# Schematic.net
KiCad netlist of a schematic drawn in Altium Designer
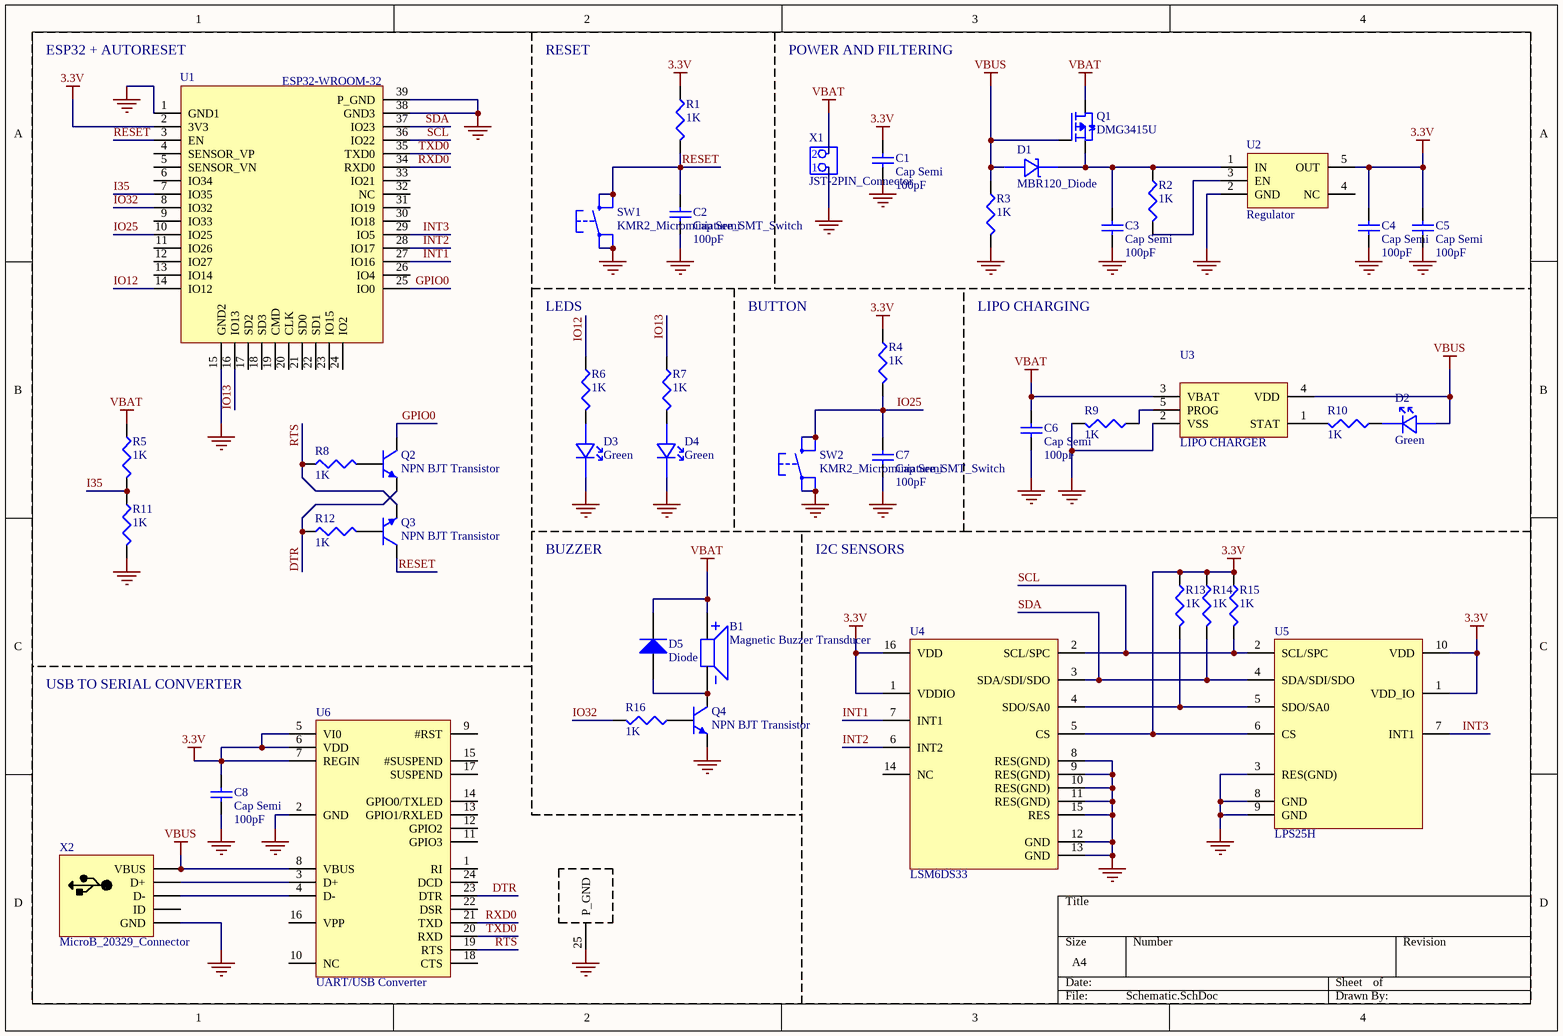
[diagram p0: Schematic.SchDoc]

(export (version "E")
  (design (tool "Eeschema 10.0.6"))
  (components
    (comp (ref "B1")
      (value "Magnetic Buzzer Transducer")
      (footprint "CMT-0502 Buzzer")
      (libsource (lib "Custom WROOM32 Board Library") (part "CMT-0502-75-SMT-TR"))
    )
    (comp (ref "C1")
      (value "Cap Semi")
      (footprint "J1-0603")
      (description "Capacitor (Semiconductor SIM Model)")
      (fields (field (name "ALTIUM_VALUE") "100pF") (field (name "PUBLISHER") "Altium Limited"))
      (libsource (lib "Miscellaneous Devices") (part "Cap Semi"))
    )
    (comp (ref "C2")
      (value "Cap Semi")
      (footprint "J1-0603")
      (description "Capacitor (Semiconductor SIM Model)")
      (fields (field (name "ALTIUM_VALUE") "100pF") (field (name "PUBLISHER") "Altium Limited"))
      (libsource (lib "Miscellaneous Devices") (part "Cap Semi"))
    )
    (comp (ref "C3")
      (value "Cap Semi")
      (footprint "J1-0603")
      (description "Capacitor (Semiconductor SIM Model)")
      (fields (field (name "ALTIUM_VALUE") "100pF") (field (name "PUBLISHER") "Altium Limited"))
      (libsource (lib "Miscellaneous Devices") (part "Cap Semi"))
    )
    (comp (ref "C4")
      (value "Cap Semi")
      (footprint "J1-0603")
      (description "Capacitor (Semiconductor SIM Model)")
      (fields (field (name "ALTIUM_VALUE") "100pF") (field (name "PUBLISHER") "Altium Limited"))
      (libsource (lib "Miscellaneous Devices") (part "Cap Semi"))
    )
    (comp (ref "C5")
      (value "Cap Semi")
      (footprint "J1-0603")
      (description "Capacitor (Semiconductor SIM Model)")
      (fields (field (name "ALTIUM_VALUE") "100pF") (field (name "PUBLISHER") "Altium Limited"))
      (libsource (lib "Miscellaneous Devices") (part "Cap Semi"))
    )
    (comp (ref "C6")
      (value "Cap Semi")
      (footprint "J1-0603")
      (description "Capacitor (Semiconductor SIM Model)")
      (fields (field (name "ALTIUM_VALUE") "100pF") (field (name "PUBLISHER") "Altium Limited"))
      (libsource (lib "Miscellaneous Devices") (part "Cap Semi"))
    )
    (comp (ref "C7")
      (value "Cap Semi")
      (footprint "J1-0603")
      (description "Capacitor (Semiconductor SIM Model)")
      (fields (field (name "ALTIUM_VALUE") "100pF") (field (name "PUBLISHER") "Altium Limited"))
      (libsource (lib "Miscellaneous Devices") (part "Cap Semi"))
    )
    (comp (ref "C8")
      (value "Cap Semi")
      (footprint "J1-0603")
      (description "Capacitor (Semiconductor SIM Model)")
      (fields (field (name "ALTIUM_VALUE") "100pF") (field (name "PUBLISHER") "Altium Limited"))
      (libsource (lib "Miscellaneous Devices") (part "Cap Semi"))
    )
    (comp (ref "D1")
      (value "MBR120_Diode")
      (footprint "SML_LED")
      (libsource (lib "Custom WROOM32 Board Library") (part "MBR120_Diode"))
    )
    (comp (ref "D2")
      (value "Green")
      (footprint "SML_LED")
      (libsource (lib "Custom WROOM32 Board Library") (part "SML-LX0603GW-TR_LED_Diode"))
    )
    (comp (ref "D3")
      (value "Green")
      (footprint "SML_LED")
      (libsource (lib "Custom WROOM32 Board Library") (part "SML-LX0603GW-TR_LED_Diode"))
    )
    (comp (ref "D4")
      (value "Green")
      (footprint "SML_LED")
      (libsource (lib "Custom WROOM32 Board Library") (part "SML-LX0603GW-TR_LED_Diode"))
    )
    (comp (ref "D5")
      (value "Diode")
      (footprint "SML_LED")
      (description "Default Diode")
      (fields (field (name "PUBLISHER") "Altium Limited"))
      (libsource (lib "Miscellaneous Devices") (part "Diode"))
    )
    (comp (ref "Q1")
      (value "DMG3415U")
      (footprint "SOT323")
      (libsource (lib "Custom WROOM32 Board Library") (part "DMG3415U"))
    )
    (comp (ref "Q2")
      (value "NPN BJT Transistor")
      (footprint "SOT323")
      (libsource (lib "Custom WROOM32 Board Library") (part "2sd1484k"))
    )
    (comp (ref "Q3")
      (value "NPN BJT Transistor")
      (footprint "SOT323")
      (libsource (lib "Custom WROOM32 Board Library") (part "2sd1484k"))
    )
    (comp (ref "Q4")
      (value "NPN BJT Transistor")
      (footprint "SOT323")
      (libsource (lib "Custom WROOM32 Board Library") (part "2sd1484k"))
    )
    (comp (ref "R1")
      (value "1K")
      (footprint "J1-0603")
      (description "Resistor")
      (fields (field (name "Comment") "Res3") (field (name "PUBLISHER") "Altium Limited"))
      (libsource (lib "Miscellaneous Devices") (part "Res3"))
    )
    (comp (ref "R2")
      (value "1K")
      (footprint "J1-0603")
      (description "Resistor")
      (fields (field (name "Comment") "Res3") (field (name "PUBLISHER") "Altium Limited"))
      (libsource (lib "Miscellaneous Devices") (part "Res3"))
    )
    (comp (ref "R3")
      (value "1K")
      (footprint "J1-0603")
      (description "Resistor")
      (fields (field (name "Comment") "Res3") (field (name "PUBLISHER") "Altium Limited"))
      (libsource (lib "Miscellaneous Devices") (part "Res3"))
    )
    (comp (ref "R4")
      (value "1K")
      (footprint "J1-0603")
      (description "Resistor")
      (fields (field (name "Comment") "Res3") (field (name "PUBLISHER") "Altium Limited"))
      (libsource (lib "Miscellaneous Devices") (part "Res3"))
    )
    (comp (ref "R5")
      (value "1K")
      (footprint "J1-0603")
      (description "Resistor")
      (fields (field (name "Comment") "Res3") (field (name "PUBLISHER") "Altium Limited"))
      (libsource (lib "Miscellaneous Devices") (part "Res3"))
    )
    (comp (ref "R6")
      (value "1K")
      (footprint "J1-0603")
      (description "Resistor")
      (fields (field (name "Comment") "Res3") (field (name "PUBLISHER") "Altium Limited"))
      (libsource (lib "Miscellaneous Devices") (part "Res3"))
    )
    (comp (ref "R7")
      (value "1K")
      (footprint "J1-0603")
      (description "Resistor")
      (fields (field (name "Comment") "Res3") (field (name "PUBLISHER") "Altium Limited"))
      (libsource (lib "Miscellaneous Devices") (part "Res3"))
    )
    (comp (ref "R8")
      (value "1K")
      (footprint "J1-0603")
      (description "Resistor")
      (fields (field (name "Comment") "Res3") (field (name "PUBLISHER") "Altium Limited"))
      (libsource (lib "Miscellaneous Devices") (part "Res3"))
    )
    (comp (ref "R9")
      (value "1K")
      (footprint "J1-0603")
      (description "Resistor")
      (fields (field (name "Comment") "Res3") (field (name "PUBLISHER") "Altium Limited"))
      (libsource (lib "Miscellaneous Devices") (part "Res3"))
    )
    (comp (ref "R10")
      (value "1K")
      (footprint "J1-0603")
      (description "Resistor")
      (fields (field (name "Comment") "Res3") (field (name "PUBLISHER") "Altium Limited"))
      (libsource (lib "Miscellaneous Devices") (part "Res3"))
    )
    (comp (ref "R11")
      (value "1K")
      (footprint "J1-0603")
      (description "Resistor")
      (fields (field (name "Comment") "Res3") (field (name "PUBLISHER") "Altium Limited"))
      (libsource (lib "Miscellaneous Devices") (part "Res3"))
    )
    (comp (ref "R12")
      (value "1K")
      (footprint "J1-0603")
      (description "Resistor")
      (fields (field (name "Comment") "Res3") (field (name "PUBLISHER") "Altium Limited"))
      (libsource (lib "Miscellaneous Devices") (part "Res3"))
    )
    (comp (ref "R13")
      (value "1K")
      (footprint "J1-0603")
      (description "Resistor")
      (fields (field (name "Comment") "Res3") (field (name "PUBLISHER") "Altium Limited"))
      (libsource (lib "Miscellaneous Devices") (part "Res3"))
    )
    (comp (ref "R14")
      (value "1K")
      (footprint "J1-0603")
      (description "Resistor")
      (fields (field (name "Comment") "Res3") (field (name "PUBLISHER") "Altium Limited"))
      (libsource (lib "Miscellaneous Devices") (part "Res3"))
    )
    (comp (ref "R15")
      (value "1K")
      (footprint "J1-0603")
      (description "Resistor")
      (fields (field (name "Comment") "Res3") (field (name "PUBLISHER") "Altium Limited"))
      (libsource (lib "Miscellaneous Devices") (part "Res3"))
    )
    (comp (ref "R16")
      (value "1K")
      (footprint "J1-0603")
      (description "Resistor")
      (fields (field (name "Comment") "Res3") (field (name "PUBLISHER") "Altium Limited"))
      (libsource (lib "Miscellaneous Devices") (part "Res3"))
    )
    (comp (ref "SW1")
      (value "KMR2_Microminiature_SMT_Switch")
      (footprint "KMR 2 Microswitch")
      (libsource (lib "Custom WROOM32 Board Library") (part "KMR2_Microminiature_SMT_Switch"))
    )
    (comp (ref "SW2")
      (value "KMR2_Microminiature_SMT_Switch")
      (footprint "KMR 2 Microswitch")
      (libsource (lib "Custom WROOM32 Board Library") (part "KMR2_Microminiature_SMT_Switch"))
    )
    (comp (ref "U1")
      (value "ESP32-WROOM-32")
      (footprint "ESP_WROOM_32")
      (libsource (lib "Custom WROOM32 Board Library") (part "ESP32-WROOM-32"))
    )
    (comp (ref "U2")
      (value "Regulator")
      (footprint "SOT25")
      (libsource (lib "Custom WROOM32 Board Library") (part "AP2112-3.3"))
    )
    (comp (ref "U3")
      (value "LIPO CHARGER")
      (footprint "SOT-23")
      (libsource (lib "Custom WROOM32 Board Library") (part "MCP7381/2"))
    )
    (comp (ref "U4")
      (value "LSM6DS33")
      (footprint "LSM6DS33")
      (libsource (lib "Custom WROOM32 Board Library") (part "LSM6DS33"))
    )
    (comp (ref "U5")
      (value "LPS25H")
      (footprint "LPS25HB")
      (libsource (lib "Custom WROOM32 Board Library") (part "LPS25H"))
    )
    (comp (ref "U6")
      (value "UART/USB Converter")
      (footprint "CP2104-GM")
      (libsource (lib "Custom WROOM32 Board Library") (part "CP2104"))
    )
    (comp (ref "X1")
      (value "JST-2PIN_Connector")
      (footprint "JST-2PIN")
      (libsource (lib "Custom WROOM32 Board Library") (part "JST-2PIN_Connector"))
    )
    (comp (ref "X2")
      (value "MicroB_20329_Connector")
      (footprint "Micro_B_USB_smd")
      (libsource (lib "Custom WROOM32 Board Library") (part "MicroB_20329_Connector"))
    )
  )
  (nets
    (net (code "1") (name "/DTR") (class "Default")
      (node (ref "Q2") (pin "1") (pinfunction "E_1") (pintype "passive"))
      (node (ref "R12") (pin "1") (pinfunction "1_1") (pintype "passive"))
      (node (ref "U6") (pin "23") (pinfunction "DTR_23") (pintype "passive"))
    )
    (net (code "2") (name "/GPIO0") (class "Default")
      (node (ref "Q2") (pin "3") (pinfunction "C_3") (pintype "passive"))
      (node (ref "U1") (pin "25") (pinfunction "IO0_25") (pintype "passive"))
    )
    (net (code "3") (name "/I35") (class "Default")
      (node (ref "R11") (pin "1") (pinfunction "1_1") (pintype "passive"))
      (node (ref "R5") (pin "2") (pinfunction "2_2") (pintype "passive"))
      (node (ref "U1") (pin "7") (pinfunction "IO35_7") (pintype "passive"))
    )
    (net (code "4") (name "/INT1") (class "Default")
      (node (ref "U1") (pin "27") (pinfunction "IO16_27") (pintype "passive"))
      (node (ref "U4") (pin "7") (pinfunction "INT1_7") (pintype "passive"))
    )
    (net (code "5") (name "/INT2") (class "Default")
      (node (ref "U1") (pin "28") (pinfunction "IO17_28") (pintype "passive"))
      (node (ref "U4") (pin "6") (pinfunction "INT2_6") (pintype "passive"))
    )
    (net (code "6") (name "/INT3") (class "Default")
      (node (ref "U1") (pin "29") (pinfunction "IO5_29") (pintype "passive"))
      (node (ref "U5") (pin "7") (pinfunction "INT1_7") (pintype "passive"))
    )
    (net (code "7") (name "/IO12") (class "Default")
      (node (ref "R6") (pin "1") (pinfunction "1_1") (pintype "passive"))
      (node (ref "U1") (pin "14") (pinfunction "IO12_14") (pintype "passive"))
    )
    (net (code "8") (name "/IO13") (class "Default")
      (node (ref "R7") (pin "1") (pinfunction "1_1") (pintype "passive"))
      (node (ref "U1") (pin "16") (pinfunction "IO13_16") (pintype "passive"))
    )
    (net (code "9") (name "/IO25") (class "Default")
      (node (ref "C7") (pin "2") (pinfunction "2_2") (pintype "passive"))
      (node (ref "R4") (pin "2") (pinfunction "2_2") (pintype "passive"))
      (node (ref "SW2") (pin "1") (pinfunction "1_1") (pintype "passive"))
      (node (ref "SW2") (pin "2") (pinfunction "2_2") (pintype "passive"))
      (node (ref "U1") (pin "10") (pinfunction "IO25_10") (pintype "passive"))
    )
    (net (code "10") (name "/IO32") (class "Default")
      (node (ref "R16") (pin "2") (pinfunction "2_2") (pintype "passive"))
      (node (ref "U1") (pin "8") (pinfunction "IO32_8") (pintype "passive"))
    )
    (net (code "11") (name "/RESET") (class "Default")
      (node (ref "C2") (pin "2") (pinfunction "2_2") (pintype "passive"))
      (node (ref "Q3") (pin "3") (pinfunction "C_3") (pintype "passive"))
      (node (ref "R1") (pin "2") (pinfunction "2_2") (pintype "passive"))
      (node (ref "SW1") (pin "1") (pinfunction "1_1") (pintype "passive"))
      (node (ref "SW1") (pin "2") (pinfunction "2_2") (pintype "passive"))
      (node (ref "U1") (pin "3") (pinfunction "EN_3") (pintype "passive"))
    )
    (net (code "12") (name "/RTS") (class "Default")
      (node (ref "Q3") (pin "1") (pinfunction "E_1") (pintype "passive"))
      (node (ref "R8") (pin "1") (pinfunction "1_1") (pintype "passive"))
      (node (ref "U6") (pin "19") (pinfunction "RTS_19") (pintype "passive"))
    )
    (net (code "13") (name "/RXD0") (class "Default")
      (node (ref "U1") (pin "34") (pinfunction "RXD0_34") (pintype "passive"))
      (node (ref "U6") (pin "21") (pinfunction "TXD_21") (pintype "passive"))
    )
    (net (code "14") (name "/SCL") (class "Default")
      (node (ref "R15") (pin "1") (pinfunction "1_1") (pintype "passive"))
      (node (ref "U1") (pin "36") (pinfunction "IO22_36") (pintype "passive"))
      (node (ref "U4") (pin "2") (pinfunction "SCL/SPC_2") (pintype "passive"))
      (node (ref "U5") (pin "2") (pinfunction "SCL/SPC_2") (pintype "passive"))
    )
    (net (code "15") (name "/SDA") (class "Default")
      (node (ref "R14") (pin "1") (pinfunction "1_1") (pintype "passive"))
      (node (ref "U1") (pin "37") (pinfunction "IO23_37") (pintype "passive"))
      (node (ref "U4") (pin "3") (pinfunction "SDA/SDI/SDO_3") (pintype "passive"))
      (node (ref "U5") (pin "4") (pinfunction "SDA/SDI/SDO_4") (pintype "passive"))
    )
    (net (code "16") (name "/TXD0") (class "Default")
      (node (ref "U1") (pin "35") (pinfunction "TXD0_35") (pintype "passive"))
      (node (ref "U6") (pin "20") (pinfunction "RXD_20") (pintype "passive"))
    )
    (net (code "17") (name "3.3V") (class "Default")
      (node (ref "C1") (pin "2") (pinfunction "2_2") (pintype "passive"))
      (node (ref "C4") (pin "2") (pinfunction "2_2") (pintype "passive"))
      (node (ref "C5") (pin "2") (pinfunction "2_2") (pintype "passive"))
      (node (ref "C8") (pin "2") (pinfunction "2_2") (pintype "passive"))
      (node (ref "R1") (pin "1") (pinfunction "1_1") (pintype "passive"))
      (node (ref "R13") (pin "2") (pinfunction "2_2") (pintype "passive"))
      (node (ref "R14") (pin "2") (pinfunction "2_2") (pintype "passive"))
      (node (ref "R15") (pin "2") (pinfunction "2_2") (pintype "passive"))
      (node (ref "R4") (pin "1") (pinfunction "1_1") (pintype "passive"))
      (node (ref "U1") (pin "2") (pinfunction "3V3_2") (pintype "passive"))
      (node (ref "U2") (pin "5") (pinfunction "OUT_5") (pintype "passive"))
      (node (ref "U4") (pin "1") (pinfunction "VDDIO_1") (pintype "passive"))
      (node (ref "U4") (pin "16") (pinfunction "VDD_16") (pintype "passive"))
      (node (ref "U4") (pin "5") (pinfunction "CS_5") (pintype "passive"))
      (node (ref "U5") (pin "1") (pinfunction "VDD_IO_1") (pintype "passive"))
      (node (ref "U5") (pin "10") (pinfunction "VDD_10") (pintype "passive"))
      (node (ref "U5") (pin "6") (pinfunction "CS_6") (pintype "passive"))
      (node (ref "U6") (pin "5") (pinfunction "VI0_5") (pintype "passive"))
      (node (ref "U6") (pin "6") (pinfunction "VDD_6") (pintype "passive"))
      (node (ref "U6") (pin "7") (pinfunction "REGIN_7") (pintype "passive"))
    )
    (net (code "18") (name "GND") (class "Default")
      (node (ref "C1") (pin "1") (pinfunction "1_1") (pintype "passive"))
      (node (ref "C2") (pin "1") (pinfunction "1_1") (pintype "passive"))
      (node (ref "C3") (pin "1") (pinfunction "1_1") (pintype "passive"))
      (node (ref "C4") (pin "1") (pinfunction "1_1") (pintype "passive"))
      (node (ref "C5") (pin "1") (pinfunction "1_1") (pintype "passive"))
      (node (ref "C6") (pin "1") (pinfunction "1_1") (pintype "passive"))
      (node (ref "C7") (pin "1") (pinfunction "1_1") (pintype "passive"))
      (node (ref "C8") (pin "1") (pinfunction "1_1") (pintype "passive"))
      (node (ref "D3") (pin "2") (pinfunction "K_2") (pintype "passive"))
      (node (ref "D4") (pin "2") (pinfunction "K_2") (pintype "passive"))
      (node (ref "Q4") (pin "1") (pinfunction "E_1") (pintype "passive"))
      (node (ref "R11") (pin "2") (pinfunction "2_2") (pintype "passive"))
      (node (ref "R3") (pin "2") (pinfunction "2_2") (pintype "passive"))
      (node (ref "R9") (pin "1") (pinfunction "1_1") (pintype "passive"))
      (node (ref "SW1") (pin "3") (pinfunction "3_3") (pintype "passive"))
      (node (ref "SW1") (pin "4") (pinfunction "4_4") (pintype "passive"))
      (node (ref "SW2") (pin "3") (pinfunction "3_3") (pintype "passive"))
      (node (ref "SW2") (pin "4") (pinfunction "4_4") (pintype "passive"))
      (node (ref "U1") (pin "1") (pinfunction "GND1_1") (pintype "passive"))
      (node (ref "U1") (pin "15") (pinfunction "GND2_15") (pintype "passive"))
      (node (ref "U1") (pin "38") (pinfunction "GND3_38") (pintype "passive"))
      (node (ref "U1") (pin "39") (pinfunction "P_GND_39") (pintype "passive"))
      (node (ref "U2") (pin "2") (pinfunction "GND_2") (pintype "passive"))
      (node (ref "U3") (pin "2") (pinfunction "VSS_2") (pintype "passive"))
      (node (ref "U4") (pin "10") (pinfunction "RES(GND)_10") (pintype "passive"))
      (node (ref "U4") (pin "11") (pinfunction "RES(GND)_11") (pintype "passive"))
      (node (ref "U4") (pin "12") (pinfunction "GND_12") (pintype "passive"))
      (node (ref "U4") (pin "13") (pinfunction "GND_13") (pintype "passive"))
      (node (ref "U4") (pin "15") (pinfunction "RES_15") (pintype "passive"))
      (node (ref "U4") (pin "8") (pinfunction "RES(GND)_8") (pintype "passive"))
      (node (ref "U4") (pin "9") (pinfunction "RES(GND)_9") (pintype "passive"))
      (node (ref "U5") (pin "3") (pinfunction "RES(GND)_3") (pintype "passive"))
      (node (ref "U5") (pin "8") (pinfunction "GND_8") (pintype "passive"))
      (node (ref "U5") (pin "9") (pinfunction "GND_9") (pintype "passive"))
      (node (ref "U6") (pin "2") (pinfunction "GND_2") (pintype "passive"))
      (node (ref "U6") (pin "25") (pinfunction "P_GND_25") (pintype "passive"))
      (node (ref "X1") (pin "1") (pinfunction "1_1") (pintype "passive"))
      (node (ref "X2") (pin "5") (pinfunction "GND_5") (pintype "passive"))
    )
    (net (code "19") (name "Net-(B1--)") (class "Default")
      (node (ref "B1") (pin "2") (pinfunction "-_2") (pintype "passive"))
      (node (ref "D5") (pin "1") (pinfunction "A_1") (pintype "passive"))
      (node (ref "Q4") (pin "3") (pinfunction "C_3") (pintype "passive"))
    )
    (net (code "20") (name "Net-(D1-K)") (class "Default")
      (node (ref "C3") (pin "2") (pinfunction "2_2") (pintype "passive"))
      (node (ref "D1") (pin "2") (pinfunction "K_2") (pintype "passive"))
      (node (ref "Q1") (pin "3") (pinfunction "S_3") (pintype "passive"))
      (node (ref "R2") (pin "1") (pinfunction "1_1") (pintype "passive"))
      (node (ref "U2") (pin "1") (pinfunction "IN_1") (pintype "passive"))
    )
    (net (code "21") (name "Net-(D2-K)") (class "Default")
      (node (ref "D2") (pin "2") (pinfunction "K_2") (pintype "passive"))
      (node (ref "R10") (pin "2") (pinfunction "2_2") (pintype "passive"))
    )
    (net (code "22") (name "Net-(D3-A)") (class "Default")
      (node (ref "D3") (pin "1") (pinfunction "A_1") (pintype "passive"))
      (node (ref "R6") (pin "2") (pinfunction "2_2") (pintype "passive"))
    )
    (net (code "23") (name "Net-(D4-A)") (class "Default")
      (node (ref "D4") (pin "1") (pinfunction "A_1") (pintype "passive"))
      (node (ref "R7") (pin "2") (pinfunction "2_2") (pintype "passive"))
    )
    (net (code "24") (name "Net-(Q2-B)") (class "Default")
      (node (ref "Q2") (pin "2") (pinfunction "B_2") (pintype "passive"))
      (node (ref "R8") (pin "2") (pinfunction "2_2") (pintype "passive"))
    )
    (net (code "25") (name "Net-(Q3-B)") (class "Default")
      (node (ref "Q3") (pin "2") (pinfunction "B_2") (pintype "passive"))
      (node (ref "R12") (pin "2") (pinfunction "2_2") (pintype "passive"))
    )
    (net (code "26") (name "Net-(Q4-B)") (class "Default")
      (node (ref "Q4") (pin "2") (pinfunction "B_2") (pintype "passive"))
      (node (ref "R16") (pin "1") (pinfunction "1_1") (pintype "passive"))
    )
    (net (code "27") (name "Net-(U2-EN)") (class "Default")
      (node (ref "R2") (pin "2") (pinfunction "2_2") (pintype "passive"))
      (node (ref "U2") (pin "3") (pinfunction "EN_3") (pintype "passive"))
    )
    (net (code "28") (name "Net-(U3-PROG)") (class "Default")
      (node (ref "R9") (pin "2") (pinfunction "2_2") (pintype "passive"))
      (node (ref "U3") (pin "5") (pinfunction "PROG_5") (pintype "passive"))
    )
    (net (code "29") (name "Net-(U3-STAT)") (class "Default")
      (node (ref "R10") (pin "1") (pinfunction "1_1") (pintype "passive"))
      (node (ref "U3") (pin "1") (pinfunction "STAT_1") (pintype "passive"))
    )
    (net (code "30") (name "Net-(U4-SDO{slash}SA0)") (class "Default")
      (node (ref "R13") (pin "1") (pinfunction "1_1") (pintype "passive"))
      (node (ref "U4") (pin "4") (pinfunction "SDO/SA0_4") (pintype "passive"))
      (node (ref "U5") (pin "5") (pinfunction "SDO/SA0_5") (pintype "passive"))
    )
    (net (code "31") (name "Net-(U6-D+)") (class "Default")
      (node (ref "U6") (pin "3") (pinfunction "D+_3") (pintype "passive"))
      (node (ref "X2") (pin "2") (pinfunction "D+_2") (pintype "passive"))
    )
    (net (code "32") (name "Net-(U6-D-)") (class "Default")
      (node (ref "U6") (pin "4") (pinfunction "D-_4") (pintype "passive"))
      (node (ref "X2") (pin "3") (pinfunction "D-_3") (pintype "passive"))
    )
    (net (code "33") (name "VBAT") (class "Default")
      (node (ref "B1") (pin "1") (pinfunction "+_1") (pintype "passive"))
      (node (ref "C6") (pin "2") (pinfunction "2_2") (pintype "passive"))
      (node (ref "D5") (pin "2") (pinfunction "K_2") (pintype "passive"))
      (node (ref "Q1") (pin "1") (pinfunction "D_1") (pintype "passive"))
      (node (ref "R5") (pin "1") (pinfunction "1_1") (pintype "passive"))
      (node (ref "U3") (pin "3") (pinfunction "VBAT_3") (pintype "passive"))
      (node (ref "X1") (pin "2") (pinfunction "2_2") (pintype "passive"))
    )
    (net (code "34") (name "VBUS") (class "Default")
      (node (ref "D1") (pin "1") (pinfunction "A_1") (pintype "passive"))
      (node (ref "D2") (pin "1") (pinfunction "A_1") (pintype "passive"))
      (node (ref "Q1") (pin "2") (pinfunction "G_2") (pintype "passive"))
      (node (ref "R3") (pin "1") (pinfunction "1_1") (pintype "passive"))
      (node (ref "U3") (pin "4") (pinfunction "VDD_4") (pintype "passive"))
      (node (ref "U6") (pin "8") (pinfunction "VBUS_8") (pintype "passive"))
      (node (ref "X2") (pin "1") (pinfunction "VBUS_1") (pintype "passive"))
    )
    (net (code "35") (name "unconnected-(U1-CLK-Pad20)") (class "Default")
      (node (ref "U1") (pin "20") (pinfunction "CLK_20") (pintype "passive"))
    )
    (net (code "36") (name "unconnected-(U1-CMD-Pad19)") (class "Default")
      (node (ref "U1") (pin "19") (pinfunction "CMD_19") (pintype "passive"))
    )
    (net (code "37") (name "unconnected-(U1-IO2-Pad24)") (class "Default")
      (node (ref "U1") (pin "24") (pinfunction "IO2_24") (pintype "passive"))
    )
    (net (code "38") (name "unconnected-(U1-IO4-Pad26)") (class "Default")
      (node (ref "U1") (pin "26") (pinfunction "IO4_26") (pintype "passive"))
    )
    (net (code "39") (name "unconnected-(U1-IO14-Pad13)") (class "Default")
      (node (ref "U1") (pin "13") (pinfunction "IO14_13") (pintype "passive"))
    )
    (net (code "40") (name "unconnected-(U1-IO15-Pad23)") (class "Default")
      (node (ref "U1") (pin "23") (pinfunction "IO15_23") (pintype "passive"))
    )
    (net (code "41") (name "unconnected-(U1-IO18-Pad30)") (class "Default")
      (node (ref "U1") (pin "30") (pinfunction "IO18_30") (pintype "passive"))
    )
    (net (code "42") (name "unconnected-(U1-IO19-Pad31)") (class "Default")
      (node (ref "U1") (pin "31") (pinfunction "IO19_31") (pintype "passive"))
    )
    (net (code "43") (name "unconnected-(U1-IO21-Pad33)") (class "Default")
      (node (ref "U1") (pin "33") (pinfunction "IO21_33") (pintype "passive"))
    )
    (net (code "44") (name "unconnected-(U1-IO26-Pad11)") (class "Default")
      (node (ref "U1") (pin "11") (pinfunction "IO26_11") (pintype "passive"))
    )
    (net (code "45") (name "unconnected-(U1-IO27-Pad12)") (class "Default")
      (node (ref "U1") (pin "12") (pinfunction "IO27_12") (pintype "passive"))
    )
    (net (code "46") (name "unconnected-(U1-IO33-Pad9)") (class "Default")
      (node (ref "U1") (pin "9") (pinfunction "IO33_9") (pintype "passive"))
    )
    (net (code "47") (name "unconnected-(U1-IO34-Pad6)") (class "Default")
      (node (ref "U1") (pin "6") (pinfunction "IO34_6") (pintype "passive"))
    )
    (net (code "48") (name "unconnected-(U1-NC-Pad32)") (class "Default")
      (node (ref "U1") (pin "32") (pinfunction "NC_32") (pintype "passive"))
    )
    (net (code "49") (name "unconnected-(U1-SD0-Pad21)") (class "Default")
      (node (ref "U1") (pin "21") (pinfunction "SD0_21") (pintype "passive"))
    )
    (net (code "50") (name "unconnected-(U1-SD1-Pad22)") (class "Default")
      (node (ref "U1") (pin "22") (pinfunction "SD1_22") (pintype "passive"))
    )
    (net (code "51") (name "unconnected-(U1-SD2-Pad17)") (class "Default")
      (node (ref "U1") (pin "17") (pinfunction "SD2_17") (pintype "passive"))
    )
    (net (code "52") (name "unconnected-(U1-SD3-Pad18)") (class "Default")
      (node (ref "U1") (pin "18") (pinfunction "SD3_18") (pintype "passive"))
    )
    (net (code "53") (name "unconnected-(U1-SENSOR_VN-Pad5)") (class "Default")
      (node (ref "U1") (pin "5") (pinfunction "SENSOR_VN_5") (pintype "passive"))
    )
    (net (code "54") (name "unconnected-(U1-SENSOR_VP-Pad4)") (class "Default")
      (node (ref "U1") (pin "4") (pinfunction "SENSOR_VP_4") (pintype "passive"))
    )
    (net (code "55") (name "unconnected-(U2-NC-Pad4)") (class "Default")
      (node (ref "U2") (pin "4") (pinfunction "NC_4") (pintype "passive"))
    )
    (net (code "56") (name "unconnected-(U4-NC-Pad14)") (class "Default")
      (node (ref "U4") (pin "14") (pinfunction "NC_14") (pintype "passive"))
    )
    (net (code "57") (name "unconnected-(U6-#RST-Pad9)") (class "Default")
      (node (ref "U6") (pin "9") (pinfunction "#RST_9") (pintype "passive"))
    )
    (net (code "58") (name "unconnected-(U6-#SUSPEND-Pad15)") (class "Default")
      (node (ref "U6") (pin "15") (pinfunction "#SUSPEND_15") (pintype "passive"))
    )
    (net (code "59") (name "unconnected-(U6-CTS-Pad18)") (class "Default")
      (node (ref "U6") (pin "18") (pinfunction "CTS_18") (pintype "passive"))
    )
    (net (code "60") (name "unconnected-(U6-DCD-Pad24)") (class "Default")
      (node (ref "U6") (pin "24") (pinfunction "DCD_24") (pintype "passive"))
    )
    (net (code "61") (name "unconnected-(U6-DSR-Pad22)") (class "Default")
      (node (ref "U6") (pin "22") (pinfunction "DSR_22") (pintype "passive"))
    )
    (net (code "62") (name "unconnected-(U6-GPIO0{slash}TXLED-Pad14)") (class "Default")
      (node (ref "U6") (pin "14") (pinfunction "GPIO0/TXLED_14") (pintype "passive"))
    )
    (net (code "63") (name "unconnected-(U6-GPIO1{slash}RXLED-Pad13)") (class "Default")
      (node (ref "U6") (pin "13") (pinfunction "GPIO1/RXLED_13") (pintype "passive"))
    )
    (net (code "64") (name "unconnected-(U6-GPIO2-Pad12)") (class "Default")
      (node (ref "U6") (pin "12") (pinfunction "GPIO2_12") (pintype "passive"))
    )
    (net (code "65") (name "unconnected-(U6-GPIO3-Pad11)") (class "Default")
      (node (ref "U6") (pin "11") (pinfunction "GPIO3_11") (pintype "passive"))
    )
    (net (code "66") (name "unconnected-(U6-NC-Pad10)") (class "Default")
      (node (ref "U6") (pin "10") (pinfunction "NC_10") (pintype "passive"))
    )
    (net (code "67") (name "unconnected-(U6-RI-Pad1)") (class "Default")
      (node (ref "U6") (pin "1") (pinfunction "RI_1") (pintype "passive"))
    )
    (net (code "68") (name "unconnected-(U6-SUSPEND-Pad17)") (class "Default")
      (node (ref "U6") (pin "17") (pinfunction "SUSPEND_17") (pintype "passive"))
    )
    (net (code "69") (name "unconnected-(U6-VPP-Pad16)") (class "Default")
      (node (ref "U6") (pin "16") (pinfunction "VPP_16") (pintype "passive"))
    )
    (net (code "70") (name "unconnected-(X2-ID-Pad4)") (class "Default")
      (node (ref "X2") (pin "4") (pinfunction "ID_4") (pintype "passive"))
    )
  )
)
